# Oled.net
KiCad netlist of a schematic drawn in Altium Designer
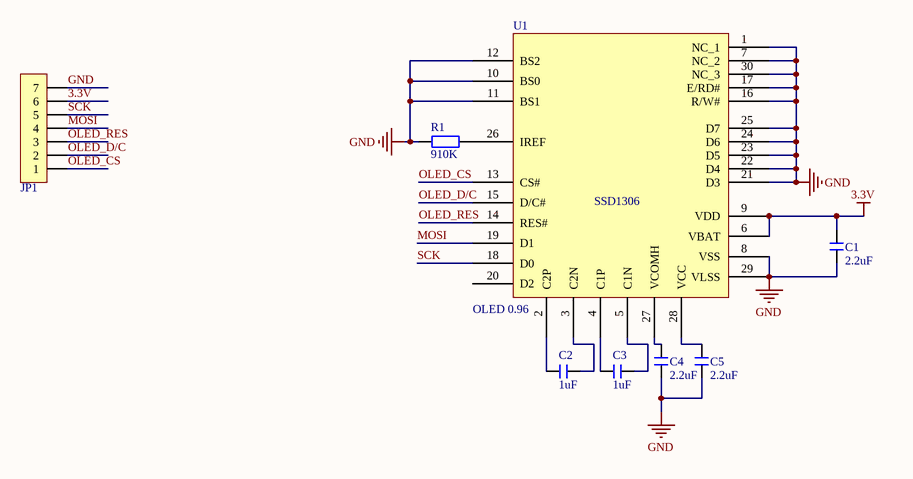
[diagram p0: Oled.SchDoc]

(export (version "E")
  (design (tool "Eeschema 10.0.6"))
  (components
    (comp (ref "C1")
      (value "2.2uF")
      (footprint "C 0603")
      (description "无极性贴片电容")
      (fields (field (name "版权归属") "黎明电子style"))
      (libsource (lib "电阻-电容-电感") (part "C"))
    )
    (comp (ref "C2")
      (value "1uF")
      (footprint "C 0603")
      (description "无极性贴片电容")
      (fields (field (name "版权归属") "黎明电子style"))
      (libsource (lib "电阻-电容-电感") (part "C"))
    )
    (comp (ref "C3")
      (value "1uF")
      (footprint "C 0603")
      (description "无极性贴片电容")
      (fields (field (name "版权归属") "黎明电子style"))
      (libsource (lib "电阻-电容-电感") (part "C"))
    )
    (comp (ref "C4")
      (value "2.2uF")
      (footprint "C 0603")
      (description "无极性贴片电容")
      (fields (field (name "版权归属") "黎明电子style"))
      (libsource (lib "电阻-电容-电感") (part "C"))
    )
    (comp (ref "C5")
      (value "2.2uF")
      (footprint "C 0603")
      (description "无极性贴片电容")
      (fields (field (name "版权归属") "黎明电子style"))
      (libsource (lib "电阻-电容-电感") (part "C"))
    )
    (comp (ref "JP1")
      (value "HDR-1X7")
      (footprint "HDR2.54 ST 1x7 H")
      (description "7P接插件")
      (fields (field (name "版权归属") "黎明电子style"))
      (libsource (lib "接插件") (part "Header 7"))
    )
    (comp (ref "R1")
      (value "910K")
      (footprint "R 0603")
      (description "贴片电阻")
      (fields (field (name "版权归属") "黎明电子style"))
      (libsource (lib "电阻-电容-电感") (part "R"))
    )
    (comp (ref "U1")
      (value "OLED 0.96")
      (footprint "OLED 0.96 - TWO")
      (libsource (lib "显示器件") (part "OLED 0.96"))
    )
  )
  (nets
    (net (code "1") (name "/MOSI") (class "Default")
      (node (ref "JP1") (pin "4") (pinfunction "4_4") (pintype "passive"))
      (node (ref "U1") (pin "19") (pinfunction "D1_19") (pintype "passive"))
    )
    (net (code "2") (name "/OLED_CS") (class "Default")
      (node (ref "JP1") (pin "1") (pinfunction "1_1") (pintype "passive"))
      (node (ref "U1") (pin "13") (pinfunction "CS#_13") (pintype "passive"))
    )
    (net (code "3") (name "/OLED_D{slash}C") (class "Default")
      (node (ref "JP1") (pin "2") (pinfunction "2_2") (pintype "passive"))
      (node (ref "U1") (pin "15") (pinfunction "D/C#_15") (pintype "passive"))
    )
    (net (code "4") (name "/OLED_RES") (class "Default")
      (node (ref "JP1") (pin "3") (pinfunction "3_3") (pintype "passive"))
      (node (ref "U1") (pin "14") (pinfunction "RES#_14") (pintype "passive"))
    )
    (net (code "5") (name "/SCK") (class "Default")
      (node (ref "JP1") (pin "5") (pinfunction "5_5") (pintype "passive"))
      (node (ref "U1") (pin "18") (pinfunction "D0_18") (pintype "passive"))
    )
    (net (code "6") (name "3.3V") (class "Default")
      (node (ref "C1") (pin "2") (pinfunction "2_2") (pintype "passive"))
      (node (ref "JP1") (pin "6") (pinfunction "6_6") (pintype "passive"))
      (node (ref "U1") (pin "6") (pinfunction "VBAT_6") (pintype "passive"))
      (node (ref "U1") (pin "9") (pinfunction "VDD_9") (pintype "passive"))
    )
    (net (code "7") (name "GND") (class "Default")
      (node (ref "C1") (pin "1") (pinfunction "1_1") (pintype "passive"))
      (node (ref "C4") (pin "1") (pinfunction "1_1") (pintype "passive"))
      (node (ref "C5") (pin "1") (pinfunction "1_1") (pintype "passive"))
      (node (ref "JP1") (pin "7") (pinfunction "7_7") (pintype "passive"))
      (node (ref "R1") (pin "1") (pinfunction "1_1") (pintype "passive"))
      (node (ref "U1") (pin "1") (pinfunction "NC_1_1") (pintype "passive"))
      (node (ref "U1") (pin "10") (pinfunction "BS0_10") (pintype "passive"))
      (node (ref "U1") (pin "11") (pinfunction "BS1_11") (pintype "passive"))
      (node (ref "U1") (pin "12") (pinfunction "BS2_12") (pintype "passive"))
      (node (ref "U1") (pin "16") (pinfunction "R/W#_16") (pintype "passive"))
      (node (ref "U1") (pin "17") (pinfunction "E/RD#_17") (pintype "passive"))
      (node (ref "U1") (pin "21") (pinfunction "D3_21") (pintype "passive"))
      (node (ref "U1") (pin "22") (pinfunction "D4_22") (pintype "passive"))
      (node (ref "U1") (pin "23") (pinfunction "D5_23") (pintype "passive"))
      (node (ref "U1") (pin "24") (pinfunction "D6_24") (pintype "passive"))
      (node (ref "U1") (pin "25") (pinfunction "D7_25") (pintype "passive"))
      (node (ref "U1") (pin "29") (pinfunction "VLSS_29") (pintype "passive"))
      (node (ref "U1") (pin "30") (pinfunction "NC_3_30") (pintype "passive"))
      (node (ref "U1") (pin "7") (pinfunction "NC_2_7") (pintype "passive"))
      (node (ref "U1") (pin "8") (pinfunction "VSS_8") (pintype "passive"))
    )
    (net (code "8") (name "Net-(U1-C1N)") (class "Default")
      (node (ref "C3") (pin "2") (pinfunction "2_2") (pintype "passive"))
      (node (ref "U1") (pin "5") (pinfunction "C1N_5") (pintype "passive"))
    )
    (net (code "9") (name "Net-(U1-C1P)") (class "Default")
      (node (ref "C3") (pin "1") (pinfunction "1_1") (pintype "passive"))
      (node (ref "U1") (pin "4") (pinfunction "C1P_4") (pintype "passive"))
    )
    (net (code "10") (name "Net-(U1-C2N)") (class "Default")
      (node (ref "C2") (pin "2") (pinfunction "2_2") (pintype "passive"))
      (node (ref "U1") (pin "3") (pinfunction "C2N_3") (pintype "passive"))
    )
    (net (code "11") (name "Net-(U1-C2P)") (class "Default")
      (node (ref "C2") (pin "1") (pinfunction "1_1") (pintype "passive"))
      (node (ref "U1") (pin "2") (pinfunction "C2P_2") (pintype "passive"))
    )
    (net (code "12") (name "Net-(U1-IREF)") (class "Default")
      (node (ref "R1") (pin "2") (pinfunction "2_2") (pintype "passive"))
      (node (ref "U1") (pin "26") (pinfunction "IREF_26") (pintype "passive"))
    )
    (net (code "13") (name "Net-(U1-VCC)") (class "Default")
      (node (ref "C5") (pin "2") (pinfunction "2_2") (pintype "passive"))
      (node (ref "U1") (pin "28") (pinfunction "VCC_28") (pintype "passive"))
    )
    (net (code "14") (name "Net-(U1-VCOMH)") (class "Default")
      (node (ref "C4") (pin "2") (pinfunction "2_2") (pintype "passive"))
      (node (ref "U1") (pin "27") (pinfunction "VCOMH_27") (pintype "passive"))
    )
    (net (code "15") (name "unconnected-(U1-D2-Pad20)") (class "Default")
      (node (ref "U1") (pin "20") (pinfunction "D2_20") (pintype "passive"))
    )
  )
)
